# Test3.net
KiCad netlist of a schematic drawn in EAGLE
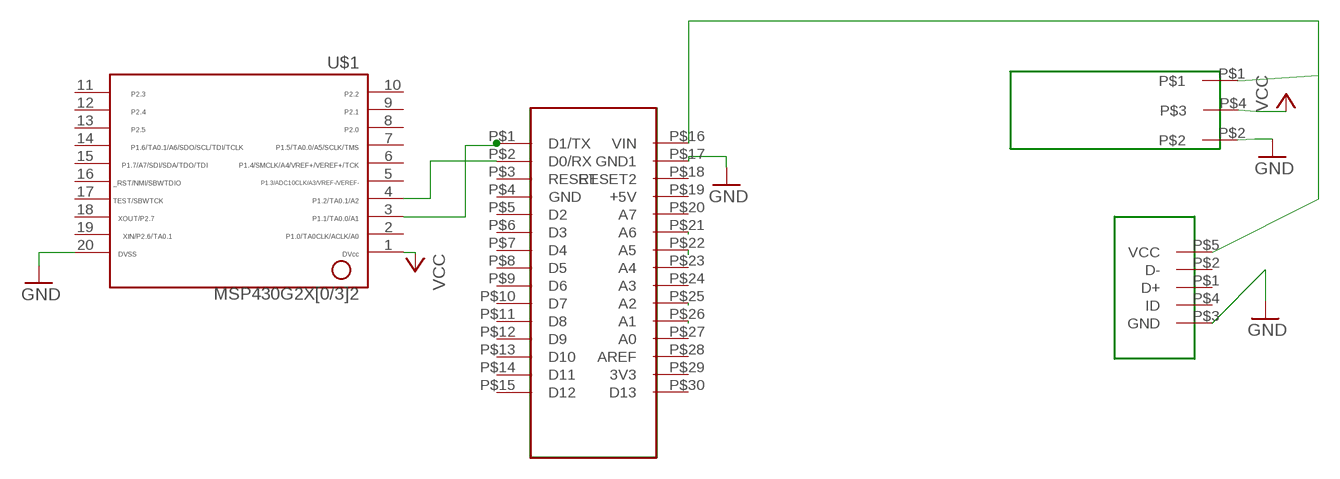
[diagram p0: schematic, sheet 1]

(export (version "E")
  (design (tool "Eeschema 10.0.6"))
  (components
    (comp (ref "U$1")
      (value "MSP430G553MSP430G2553")
      (footprint "eagle-import:MSP430G553")
      (libsource (lib "eagle-import") (part "MSP430G553MSP430G2553"))
    )
    (comp (ref "U$2")
      (value "ARDUINONANOARDUINONAONO")
      (footprint "eagle-import:ARDUINONANO")
      (libsource (lib "eagle-import") (part "ARDUINONANOARDUINONAONO"))
    )
    (comp (ref "U$5")
      (value "LMC3V3LMC3V3")
      (footprint "eagle-import:LMC3V3")
      (libsource (lib "eagle-import") (part "LMC3V3LMC3V3"))
    )
    (comp (ref "U$7")
      (value "USBUSB")
      (footprint "eagle-import:USB")
      (libsource (lib "eagle-import") (part "USBUSB"))
    )
  )
  (nets
    (net (code "1") (name "GND") (class "Default")
      (node (ref "U$1") (pin "20") (pinfunction "20_20") (pintype "bidirectional"))
      (node (ref "U$2") (pin "P$17") (pinfunction "GND1_P$17") (pintype "bidirectional"))
      (node (ref "U$5") (pin "P$2") (pinfunction "P$2_P$2") (pintype "bidirectional"))
      (node (ref "U$7") (pin "P$3") (pinfunction "GND_P$3") (pintype "bidirectional"))
    )
    (net (code "2") (name "Net-(U$2-D0{slash}RX)") (class "Default")
      (node (ref "U$1") (pin "4") (pinfunction "4_4") (pintype "bidirectional"))
      (node (ref "U$2") (pin "P$2") (pinfunction "D0/RX_P$2") (pintype "bidirectional"))
    )
    (net (code "3") (name "Net-(U$2-D1{slash}TX)") (class "Default")
      (node (ref "U$1") (pin "3") (pinfunction "3_3") (pintype "bidirectional"))
      (node (ref "U$2") (pin "P$1") (pinfunction "D1/TX_P$1") (pintype "bidirectional"))
    )
    (net (code "4") (name "Net-(U$2-VIN)") (class "Default")
      (node (ref "U$2") (pin "P$16") (pinfunction "VIN_P$16") (pintype "bidirectional"))
      (node (ref "U$5") (pin "P$1") (pinfunction "P$1_P$1") (pintype "bidirectional"))
      (node (ref "U$7") (pin "P$5") (pinfunction "VCC_P$5") (pintype "bidirectional"))
    )
    (net (code "5") (name "VCC") (class "Default")
      (node (ref "U$1") (pin "1") (pinfunction "1_1") (pintype "bidirectional"))
      (node (ref "U$5") (pin "P$4") (pinfunction "P$3_P$4") (pintype "bidirectional"))
    )
    (net (code "6") (name "unconnected-(U$1-Pad2)") (class "Default")
      (node (ref "U$1") (pin "2") (pinfunction "2_2") (pintype "bidirectional"))
    )
    (net (code "7") (name "unconnected-(U$1-Pad5)") (class "Default")
      (node (ref "U$1") (pin "5") (pinfunction "5_5") (pintype "bidirectional"))
    )
    (net (code "8") (name "unconnected-(U$1-Pad6)") (class "Default")
      (node (ref "U$1") (pin "6") (pinfunction "6_6") (pintype "bidirectional"))
    )
    (net (code "9") (name "unconnected-(U$1-Pad7)") (class "Default")
      (node (ref "U$1") (pin "7") (pinfunction "7_7") (pintype "bidirectional"))
    )
    (net (code "10") (name "unconnected-(U$1-Pad8)") (class "Default")
      (node (ref "U$1") (pin "8") (pinfunction "8_8") (pintype "bidirectional"))
    )
    (net (code "11") (name "unconnected-(U$1-Pad9)") (class "Default")
      (node (ref "U$1") (pin "9") (pinfunction "9_9") (pintype "bidirectional"))
    )
    (net (code "12") (name "unconnected-(U$1-Pad10)") (class "Default")
      (node (ref "U$1") (pin "10") (pinfunction "10_10") (pintype "bidirectional"))
    )
    (net (code "13") (name "unconnected-(U$1-Pad11)") (class "Default")
      (node (ref "U$1") (pin "11") (pinfunction "11_11") (pintype "bidirectional"))
    )
    (net (code "14") (name "unconnected-(U$1-Pad12)") (class "Default")
      (node (ref "U$1") (pin "12") (pinfunction "12_12") (pintype "bidirectional"))
    )
    (net (code "15") (name "unconnected-(U$1-Pad13)") (class "Default")
      (node (ref "U$1") (pin "13") (pinfunction "13_13") (pintype "bidirectional"))
    )
    (net (code "16") (name "unconnected-(U$1-Pad14)") (class "Default")
      (node (ref "U$1") (pin "14") (pinfunction "14_14") (pintype "bidirectional"))
    )
    (net (code "17") (name "unconnected-(U$1-Pad15)") (class "Default")
      (node (ref "U$1") (pin "15") (pinfunction "15_15") (pintype "bidirectional"))
    )
    (net (code "18") (name "unconnected-(U$1-Pad16)") (class "Default")
      (node (ref "U$1") (pin "16") (pinfunction "16_16") (pintype "bidirectional"))
    )
    (net (code "19") (name "unconnected-(U$1-Pad17)") (class "Default")
      (node (ref "U$1") (pin "17") (pinfunction "17_17") (pintype "bidirectional"))
    )
    (net (code "20") (name "unconnected-(U$1-Pad18)") (class "Default")
      (node (ref "U$1") (pin "18") (pinfunction "18_18") (pintype "bidirectional"))
    )
    (net (code "21") (name "unconnected-(U$1-Pad19)") (class "Default")
      (node (ref "U$1") (pin "19") (pinfunction "19_19") (pintype "bidirectional"))
    )
    (net (code "22") (name "unconnected-(U$2-+5V-PadP$19)") (class "Default")
      (node (ref "U$2") (pin "P$19") (pinfunction "+5V_P$19") (pintype "bidirectional"))
    )
    (net (code "23") (name "unconnected-(U$2-3V3-PadP$29)") (class "Default")
      (node (ref "U$2") (pin "P$29") (pinfunction "3V3_P$29") (pintype "bidirectional"))
    )
    (net (code "24") (name "unconnected-(U$2-A0-PadP$27)") (class "Default")
      (node (ref "U$2") (pin "P$27") (pinfunction "A0_P$27") (pintype "bidirectional"))
    )
    (net (code "25") (name "unconnected-(U$2-A1-PadP$26)") (class "Default")
      (node (ref "U$2") (pin "P$26") (pinfunction "A1_P$26") (pintype "bidirectional"))
    )
    (net (code "26") (name "unconnected-(U$2-A2-PadP$25)") (class "Default")
      (node (ref "U$2") (pin "P$25") (pinfunction "A2_P$25") (pintype "bidirectional"))
    )
    (net (code "27") (name "unconnected-(U$2-A3-PadP$24)") (class "Default")
      (node (ref "U$2") (pin "P$24") (pinfunction "A3_P$24") (pintype "bidirectional"))
    )
    (net (code "28") (name "unconnected-(U$2-A4-PadP$23)") (class "Default")
      (node (ref "U$2") (pin "P$23") (pinfunction "A4_P$23") (pintype "bidirectional"))
    )
    (net (code "29") (name "unconnected-(U$2-A5-PadP$22)") (class "Default")
      (node (ref "U$2") (pin "P$22") (pinfunction "A5_P$22") (pintype "bidirectional"))
    )
    (net (code "30") (name "unconnected-(U$2-A6-PadP$21)") (class "Default")
      (node (ref "U$2") (pin "P$21") (pinfunction "A6_P$21") (pintype "bidirectional"))
    )
    (net (code "31") (name "unconnected-(U$2-A7-PadP$20)") (class "Default")
      (node (ref "U$2") (pin "P$20") (pinfunction "A7_P$20") (pintype "bidirectional"))
    )
    (net (code "32") (name "unconnected-(U$2-AREF-PadP$28)") (class "Default")
      (node (ref "U$2") (pin "P$28") (pinfunction "AREF_P$28") (pintype "bidirectional"))
    )
    (net (code "33") (name "unconnected-(U$2-D2-PadP$5)") (class "Default")
      (node (ref "U$2") (pin "P$5") (pinfunction "D2_P$5") (pintype "bidirectional"))
    )
    (net (code "34") (name "unconnected-(U$2-D3-PadP$6)") (class "Default")
      (node (ref "U$2") (pin "P$6") (pinfunction "D3_P$6") (pintype "bidirectional"))
    )
    (net (code "35") (name "unconnected-(U$2-D4-PadP$7)") (class "Default")
      (node (ref "U$2") (pin "P$7") (pinfunction "D4_P$7") (pintype "bidirectional"))
    )
    (net (code "36") (name "unconnected-(U$2-D5-PadP$8)") (class "Default")
      (node (ref "U$2") (pin "P$8") (pinfunction "D5_P$8") (pintype "bidirectional"))
    )
    (net (code "37") (name "unconnected-(U$2-D6-PadP$9)") (class "Default")
      (node (ref "U$2") (pin "P$9") (pinfunction "D6_P$9") (pintype "bidirectional"))
    )
    (net (code "38") (name "unconnected-(U$2-D7-PadP$10)") (class "Default")
      (node (ref "U$2") (pin "P$10") (pinfunction "D7_P$10") (pintype "bidirectional"))
    )
    (net (code "39") (name "unconnected-(U$2-D8-PadP$11)") (class "Default")
      (node (ref "U$2") (pin "P$11") (pinfunction "D8_P$11") (pintype "bidirectional"))
    )
    (net (code "40") (name "unconnected-(U$2-D9-PadP$12)") (class "Default")
      (node (ref "U$2") (pin "P$12") (pinfunction "D9_P$12") (pintype "bidirectional"))
    )
    (net (code "41") (name "unconnected-(U$2-D10-PadP$13)") (class "Default")
      (node (ref "U$2") (pin "P$13") (pinfunction "D10_P$13") (pintype "bidirectional"))
    )
    (net (code "42") (name "unconnected-(U$2-D11-PadP$14)") (class "Default")
      (node (ref "U$2") (pin "P$14") (pinfunction "D11_P$14") (pintype "bidirectional"))
    )
    (net (code "43") (name "unconnected-(U$2-D12-PadP$15)") (class "Default")
      (node (ref "U$2") (pin "P$15") (pinfunction "D12_P$15") (pintype "bidirectional"))
    )
    (net (code "44") (name "unconnected-(U$2-D13-PadP$30)") (class "Default")
      (node (ref "U$2") (pin "P$30") (pinfunction "D13_P$30") (pintype "bidirectional"))
    )
    (net (code "45") (name "unconnected-(U$2-GND-PadP$4)") (class "Default")
      (node (ref "U$2") (pin "P$4") (pinfunction "GND_P$4") (pintype "bidirectional"))
    )
    (net (code "46") (name "unconnected-(U$2-RESET-PadP$3)") (class "Default")
      (node (ref "U$2") (pin "P$3") (pinfunction "RESET_P$3") (pintype "bidirectional"))
    )
    (net (code "47") (name "unconnected-(U$2-RESET2-PadP$18)") (class "Default")
      (node (ref "U$2") (pin "P$18") (pinfunction "RESET2_P$18") (pintype "bidirectional"))
    )
    (net (code "48") (name "unconnected-(U$7-D+-PadP$1)") (class "Default")
      (node (ref "U$7") (pin "P$1") (pinfunction "D+_P$1") (pintype "bidirectional"))
    )
    (net (code "49") (name "unconnected-(U$7-D--PadP$2)") (class "Default")
      (node (ref "U$7") (pin "P$2") (pinfunction "D-_P$2") (pintype "bidirectional"))
    )
    (net (code "50") (name "unconnected-(U$7-ID-PadP$4)") (class "Default")
      (node (ref "U$7") (pin "P$4") (pinfunction "ID_P$4") (pintype "bidirectional"))
    )
  )
)
